# MCU_Schematic.net
KiCad netlist of a schematic drawn in Altium Designer
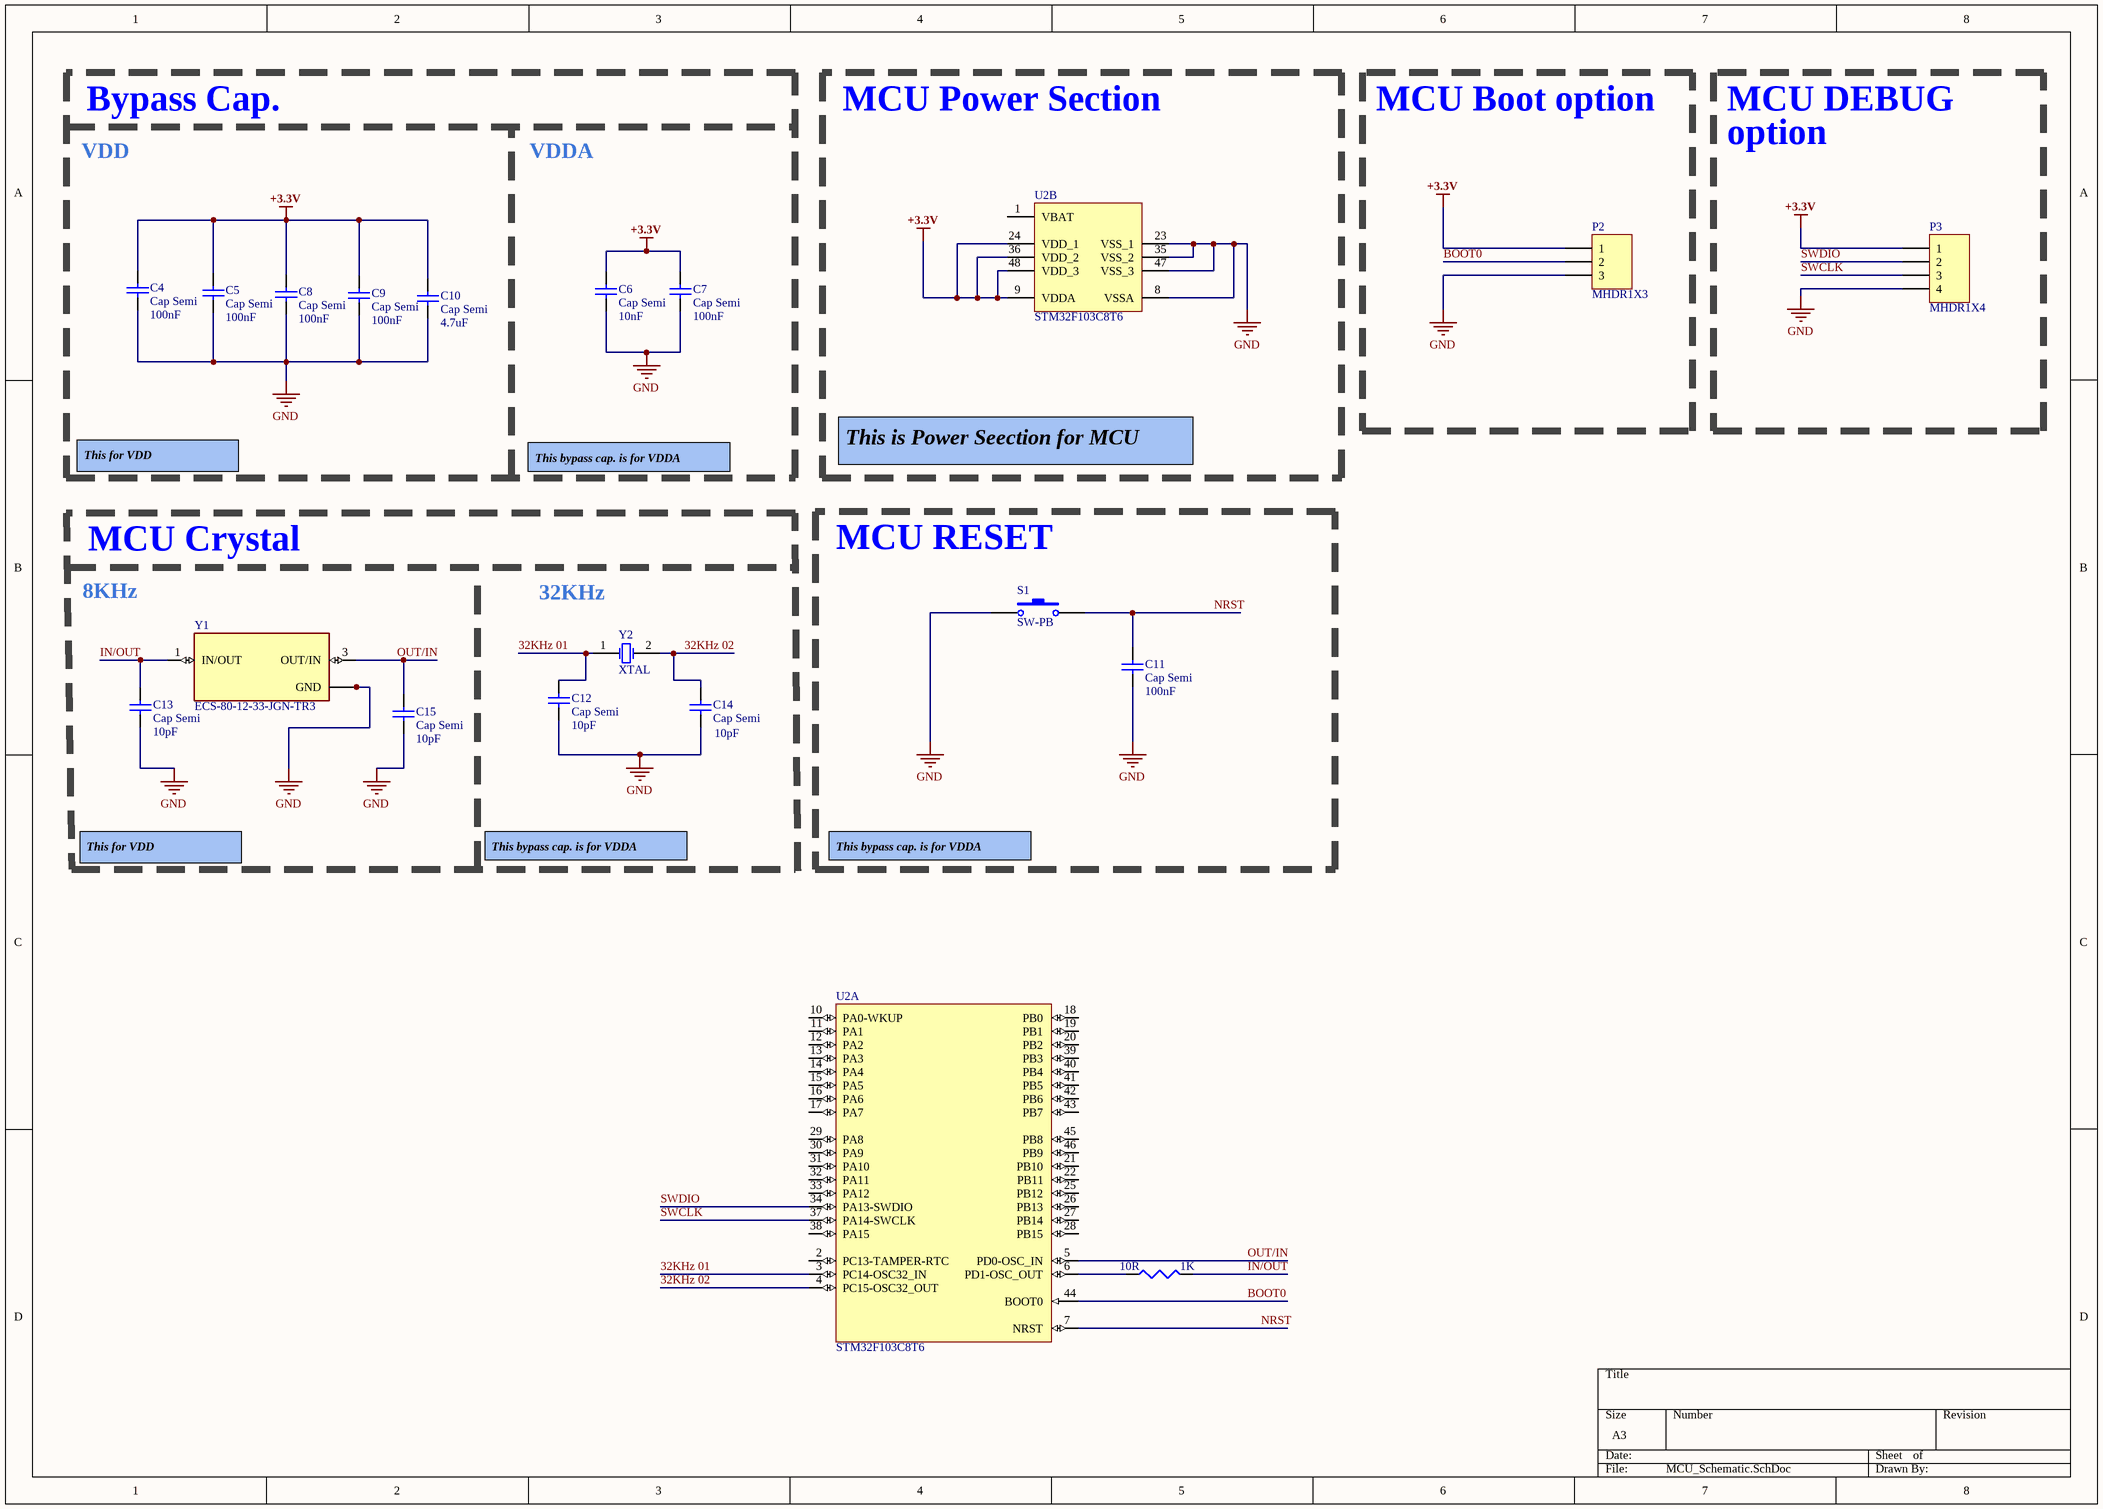
[diagram p0: MCU_Schematic.SchDoc]

(export (version "E")
  (design (tool "Eeschema 10.0.6"))
  (components
    (comp (ref "10R")
      (value "1K")
      (footprint "J1-0603")
      (description "Resistor")
      (fields (field (name "Comment") "Res3") (field (name "PUBLISHER") "Altium Limited"))
      (libsource (lib "Miscellaneous Devices") (part "Res3"))
    )
    (comp (ref "C4")
      (value "Cap Semi")
      (footprint "1608[0603]")
      (description "Capacitor (Semiconductor SIM Model)")
      (fields (field (name "ALTIUM_VALUE") "100nF") (field (name "PUBLISHER") "Altium Limited"))
      (libsource (lib "Miscellaneous Devices") (part "Cap Semi"))
    )
    (comp (ref "C5")
      (value "Cap Semi")
      (footprint "1608[0603]")
      (description "Capacitor (Semiconductor SIM Model)")
      (fields (field (name "ALTIUM_VALUE") "100nF") (field (name "PUBLISHER") "Altium Limited"))
      (libsource (lib "Miscellaneous Devices") (part "Cap Semi"))
    )
    (comp (ref "C6")
      (value "Cap Semi")
      (footprint "1608[0603]")
      (description "Capacitor (Semiconductor SIM Model)")
      (fields (field (name "ALTIUM_VALUE") "10nF") (field (name "PUBLISHER") "Altium Limited"))
      (libsource (lib "Miscellaneous Devices") (part "Cap Semi"))
    )
    (comp (ref "C7")
      (value "Cap Semi")
      (footprint "1608[0603]")
      (description "Capacitor (Semiconductor SIM Model)")
      (fields (field (name "ALTIUM_VALUE") "100nF") (field (name "PUBLISHER") "Altium Limited"))
      (libsource (lib "Miscellaneous Devices") (part "Cap Semi"))
    )
    (comp (ref "C8")
      (value "Cap Semi")
      (footprint "1608[0603]")
      (description "Capacitor (Semiconductor SIM Model)")
      (fields (field (name "ALTIUM_VALUE") "100nF") (field (name "PUBLISHER") "Altium Limited"))
      (libsource (lib "Miscellaneous Devices") (part "Cap Semi"))
    )
    (comp (ref "C9")
      (value "Cap Semi")
      (footprint "1608[0603]")
      (description "Capacitor (Semiconductor SIM Model)")
      (fields (field (name "ALTIUM_VALUE") "100nF") (field (name "PUBLISHER") "Altium Limited"))
      (libsource (lib "Miscellaneous Devices") (part "Cap Semi"))
    )
    (comp (ref "C10")
      (value "Cap Semi")
      (footprint "1608[0603]")
      (description "Capacitor (Semiconductor SIM Model)")
      (fields (field (name "ALTIUM_VALUE") "4.7uF") (field (name "PUBLISHER") "Altium Limited"))
      (libsource (lib "Miscellaneous Devices") (part "Cap Semi"))
    )
    (comp (ref "C11")
      (value "Cap Semi")
      (footprint "1608[0603]")
      (description "Capacitor (Semiconductor SIM Model)")
      (fields (field (name "ALTIUM_VALUE") "100nF") (field (name "PUBLISHER") "Altium Limited"))
      (libsource (lib "Miscellaneous Devices") (part "Cap Semi"))
    )
    (comp (ref "C12")
      (value "Cap Semi")
      (footprint "0402")
      (description "Capacitor (Semiconductor SIM Model)")
      (fields (field (name "ALTIUM_VALUE") "10pF") (field (name "PUBLISHER") "Altium Limited"))
      (libsource (lib "Miscellaneous Devices") (part "Cap Semi"))
    )
    (comp (ref "C13")
      (value "Cap Semi")
      (footprint "0402")
      (description "Capacitor (Semiconductor SIM Model)")
      (fields (field (name "ALTIUM_VALUE") "10pF") (field (name "PUBLISHER") "Altium Limited"))
      (libsource (lib "Miscellaneous Devices") (part "Cap Semi"))
    )
    (comp (ref "C14")
      (value "Cap Semi")
      (footprint "0402")
      (description "Capacitor (Semiconductor SIM Model)")
      (fields (field (name "ALTIUM_VALUE") "10pF") (field (name "PUBLISHER") "Altium Limited"))
      (libsource (lib "Miscellaneous Devices") (part "Cap Semi"))
    )
    (comp (ref "C15")
      (value "Cap Semi")
      (footprint "0402")
      (description "Capacitor (Semiconductor SIM Model)")
      (fields (field (name "ALTIUM_VALUE") "10pF") (field (name "PUBLISHER") "Altium Limited"))
      (libsource (lib "Miscellaneous Devices") (part "Cap Semi"))
    )
    (comp (ref "P2")
      (value "MHDR1X3")
      (footprint "MHDR1X3")
      (description "Header, 3-Pin")
      (fields (field (name "PUBLISHER") "Altium Limited"))
      (libsource (lib "Miscellaneous Connectors") (part "MHDR1X3"))
    )
    (comp (ref "P3")
      (value "MHDR1X4")
      (footprint "MHDR1X4")
      (description "Header, 4-Pin")
      (fields (field (name "PUBLISHER") "Altium Limited"))
      (libsource (lib "Miscellaneous Connectors") (part "MHDR1X4"))
    )
    (comp (ref "S1")
      (value "SW-PB")
      (footprint "SPST-2")
      (description "Switch")
      (fields (field (name "PUBLISHER") "Altium Limited"))
      (libsource (lib "Miscellaneous Devices") (part "SW-PB"))
    )
    (comp (ref "U2")
      (value "STM32F103C8T6")
      (footprint "LQFP48_N")
      (libsource (lib "STMicroelectronics STM32 F1") (part "STM32F103C8T6"))
    )
    (comp (ref "Y1")
      (value "ECS-80-12-33-JGN-TR3")
      (footprint "XTAL_ECS-240-8-33-AGN-TR")
      (description "Crystal 8MHz Â±20ppm (Tol) Â±30ppm (Stability) 12pF FUND 400Ohm 4-Pin Mini-CSMD T/R")
      (fields (field (name "MF") "ECS Inc."))
      (libsource (lib "ECS-80-12-33-JGN-TR3") (part "ECS-80-12-33-JGN-TR3"))
    )
    (comp (ref "Y2")
      (value "XTAL")
      (footprint "R38")
      (description "Crystal Oscillator")
      (fields (field (name "PUBLISHER") "Altium Limited"))
      (libsource (lib "Miscellaneous Devices") (part "XTAL"))
    )
  )
  (nets
    (net (code "1") (name "+3.3V") (class "Default")
      (node (ref "C10") (pin "2") (pinfunction "2_2") (pintype "passive"))
      (node (ref "C4") (pin "1") (pinfunction "1_1") (pintype "passive"))
      (node (ref "C5") (pin "2") (pinfunction "2_2") (pintype "passive"))
      (node (ref "C6") (pin "2") (pinfunction "2_2") (pintype "passive"))
      (node (ref "C7") (pin "2") (pinfunction "2_2") (pintype "passive"))
      (node (ref "C8") (pin "2") (pinfunction "2_2") (pintype "passive"))
      (node (ref "C9") (pin "2") (pinfunction "2_2") (pintype "passive"))
      (node (ref "P2") (pin "1") (pinfunction "1_1") (pintype "passive"))
      (node (ref "P3") (pin "1") (pinfunction "1_1") (pintype "passive"))
      (node (ref "U2") (pin "24") (pinfunction "VDD_1_24") (pintype "power_in"))
      (node (ref "U2") (pin "36") (pinfunction "VDD_2_36") (pintype "power_in"))
      (node (ref "U2") (pin "48") (pinfunction "VDD_3_48") (pintype "power_in"))
      (node (ref "U2") (pin "9") (pinfunction "VDDA_9") (pintype "power_in"))
    )
    (net (code "2") (name "/32KHz 01") (class "Default")
      (node (ref "C12") (pin "2") (pinfunction "2_2") (pintype "passive"))
      (node (ref "U2") (pin "3") (pinfunction "PC14-OSC32_IN_3") (pintype "bidirectional"))
      (node (ref "Y2") (pin "1") (pinfunction "OSC1_1") (pintype "passive"))
    )
    (net (code "3") (name "/32KHz 02") (class "Default")
      (node (ref "C14") (pin "2") (pinfunction "2_2") (pintype "passive"))
      (node (ref "U2") (pin "4") (pinfunction "PC15-OSC32_OUT_4") (pintype "bidirectional"))
      (node (ref "Y2") (pin "2") (pinfunction "OSC2_2") (pintype "passive"))
    )
    (net (code "4") (name "/BOOT0") (class "Default")
      (node (ref "P2") (pin "2") (pinfunction "2_2") (pintype "passive"))
      (node (ref "U2") (pin "44") (pinfunction "BOOT0_44") (pintype "input"))
    )
    (net (code "5") (name "/IN{slash}OUT") (class "Default")
      (node (ref "10R") (pin "2") (pinfunction "2_2") (pintype "passive"))
      (node (ref "C13") (pin "2") (pinfunction "2_2") (pintype "passive"))
      (node (ref "Y1") (pin "1") (pinfunction "IN/OUT_1") (pintype "bidirectional"))
    )
    (net (code "6") (name "/NRST") (class "Default")
      (node (ref "C11") (pin "2") (pinfunction "2_2") (pintype "passive"))
      (node (ref "S1") (pin "2") (pinfunction "2_2") (pintype "passive"))
      (node (ref "U2") (pin "7") (pinfunction "NRST_7") (pintype "bidirectional"))
    )
    (net (code "7") (name "/OUT{slash}IN") (class "Default")
      (node (ref "C15") (pin "2") (pinfunction "2_2") (pintype "passive"))
      (node (ref "U2") (pin "5") (pinfunction "PD0-OSC_IN_5") (pintype "bidirectional"))
      (node (ref "Y1") (pin "3") (pinfunction "OUT/IN_3") (pintype "bidirectional"))
    )
    (net (code "8") (name "/SWCLK") (class "Default")
      (node (ref "P3") (pin "3") (pinfunction "3_3") (pintype "passive"))
      (node (ref "U2") (pin "37") (pinfunction "PA14_37") (pintype "bidirectional"))
    )
    (net (code "9") (name "/SWDIO") (class "Default")
      (node (ref "P3") (pin "2") (pinfunction "2_2") (pintype "passive"))
      (node (ref "U2") (pin "34") (pinfunction "PA13_34") (pintype "bidirectional"))
    )
    (net (code "10") (name "GND") (class "Default")
      (node (ref "C10") (pin "1") (pinfunction "1_1") (pintype "passive"))
      (node (ref "C11") (pin "1") (pinfunction "1_1") (pintype "passive"))
      (node (ref "C12") (pin "1") (pinfunction "1_1") (pintype "passive"))
      (node (ref "C13") (pin "1") (pinfunction "1_1") (pintype "passive"))
      (node (ref "C14") (pin "1") (pinfunction "1_1") (pintype "passive"))
      (node (ref "C15") (pin "1") (pinfunction "1_1") (pintype "passive"))
      (node (ref "C4") (pin "2") (pinfunction "2_2") (pintype "passive"))
      (node (ref "C5") (pin "1") (pinfunction "1_1") (pintype "passive"))
      (node (ref "C6") (pin "1") (pinfunction "1_1") (pintype "passive"))
      (node (ref "C7") (pin "1") (pinfunction "1_1") (pintype "passive"))
      (node (ref "C8") (pin "1") (pinfunction "1_1") (pintype "passive"))
      (node (ref "C9") (pin "1") (pinfunction "1_1") (pintype "passive"))
      (node (ref "P2") (pin "3") (pinfunction "3_3") (pintype "passive"))
      (node (ref "P3") (pin "4") (pinfunction "4_4") (pintype "passive"))
      (node (ref "S1") (pin "1") (pinfunction "1_1") (pintype "passive"))
      (node (ref "U2") (pin "23") (pinfunction "VSS_1_23") (pintype "power_in"))
      (node (ref "U2") (pin "35") (pinfunction "VSS_2_35") (pintype "power_in"))
      (node (ref "U2") (pin "47") (pinfunction "VSS_3_47") (pintype "power_in"))
      (node (ref "U2") (pin "8") (pinfunction "VSSA_8") (pintype "power_in"))
      (node (ref "Y1") (pin "2") (pinfunction "GND_2") (pintype "power_in"))
      (node (ref "Y1") (pin "4") (pinfunction "GND_4") (pintype "power_in"))
    )
    (net (code "11") (name "Net-(U2A-PD1)") (class "Default")
      (node (ref "10R") (pin "1") (pinfunction "1_1") (pintype "passive"))
      (node (ref "U2") (pin "6") (pinfunction "PD1_6") (pintype "bidirectional"))
    )
    (net (code "12") (name "unconnected-(U2A-PA0-WKUP-Pad10)") (class "Default")
      (node (ref "U2") (pin "10") (pinfunction "PA0-WKUP_10") (pintype "bidirectional"))
    )
    (net (code "13") (name "unconnected-(U2A-PA1-Pad11)") (class "Default")
      (node (ref "U2") (pin "11") (pinfunction "PA1_11") (pintype "bidirectional"))
    )
    (net (code "14") (name "unconnected-(U2A-PA2-Pad12)") (class "Default")
      (node (ref "U2") (pin "12") (pinfunction "PA2_12") (pintype "bidirectional"))
    )
    (net (code "15") (name "unconnected-(U2A-PA3-Pad13)") (class "Default")
      (node (ref "U2") (pin "13") (pinfunction "PA3_13") (pintype "bidirectional"))
    )
    (net (code "16") (name "unconnected-(U2A-PA4-Pad14)") (class "Default")
      (node (ref "U2") (pin "14") (pinfunction "PA4_14") (pintype "bidirectional"))
    )
    (net (code "17") (name "unconnected-(U2A-PA5-Pad15)") (class "Default")
      (node (ref "U2") (pin "15") (pinfunction "PA5_15") (pintype "bidirectional"))
    )
    (net (code "18") (name "unconnected-(U2A-PA6-Pad16)") (class "Default")
      (node (ref "U2") (pin "16") (pinfunction "PA6_16") (pintype "bidirectional"))
    )
    (net (code "19") (name "unconnected-(U2A-PA7-Pad17)") (class "Default")
      (node (ref "U2") (pin "17") (pinfunction "PA7_17") (pintype "bidirectional"))
    )
    (net (code "20") (name "unconnected-(U2A-PA8-Pad29)") (class "Default")
      (node (ref "U2") (pin "29") (pinfunction "PA8_29") (pintype "bidirectional"))
    )
    (net (code "21") (name "unconnected-(U2A-PA9-Pad30)") (class "Default")
      (node (ref "U2") (pin "30") (pinfunction "PA9_30") (pintype "bidirectional"))
    )
    (net (code "22") (name "unconnected-(U2A-PA10-Pad31)") (class "Default")
      (node (ref "U2") (pin "31") (pinfunction "PA10_31") (pintype "bidirectional"))
    )
    (net (code "23") (name "unconnected-(U2A-PA11-Pad32)") (class "Default")
      (node (ref "U2") (pin "32") (pinfunction "PA11_32") (pintype "bidirectional"))
    )
    (net (code "24") (name "unconnected-(U2A-PA12-Pad33)") (class "Default")
      (node (ref "U2") (pin "33") (pinfunction "PA12_33") (pintype "bidirectional"))
    )
    (net (code "25") (name "unconnected-(U2A-PA15-Pad38)") (class "Default")
      (node (ref "U2") (pin "38") (pinfunction "PA15_38") (pintype "bidirectional"))
    )
    (net (code "26") (name "unconnected-(U2A-PB0-Pad18)") (class "Default")
      (node (ref "U2") (pin "18") (pinfunction "PB0_18") (pintype "bidirectional"))
    )
    (net (code "27") (name "unconnected-(U2A-PB1-Pad19)") (class "Default")
      (node (ref "U2") (pin "19") (pinfunction "PB1_19") (pintype "bidirectional"))
    )
    (net (code "28") (name "unconnected-(U2A-PB2-Pad20)") (class "Default")
      (node (ref "U2") (pin "20") (pinfunction "PB2_20") (pintype "bidirectional"))
    )
    (net (code "29") (name "unconnected-(U2A-PB3-Pad39)") (class "Default")
      (node (ref "U2") (pin "39") (pinfunction "PB3_39") (pintype "bidirectional"))
    )
    (net (code "30") (name "unconnected-(U2A-PB4-Pad40)") (class "Default")
      (node (ref "U2") (pin "40") (pinfunction "PB4_40") (pintype "bidirectional"))
    )
    (net (code "31") (name "unconnected-(U2A-PB5-Pad41)") (class "Default")
      (node (ref "U2") (pin "41") (pinfunction "PB5_41") (pintype "bidirectional"))
    )
    (net (code "32") (name "unconnected-(U2A-PB6-Pad42)") (class "Default")
      (node (ref "U2") (pin "42") (pinfunction "PB6_42") (pintype "bidirectional"))
    )
    (net (code "33") (name "unconnected-(U2A-PB7-Pad43)") (class "Default")
      (node (ref "U2") (pin "43") (pinfunction "PB7_43") (pintype "bidirectional"))
    )
    (net (code "34") (name "unconnected-(U2A-PB8-Pad45)") (class "Default")
      (node (ref "U2") (pin "45") (pinfunction "PB8_45") (pintype "bidirectional"))
    )
    (net (code "35") (name "unconnected-(U2A-PB9-Pad46)") (class "Default")
      (node (ref "U2") (pin "46") (pinfunction "PB9_46") (pintype "bidirectional"))
    )
    (net (code "36") (name "unconnected-(U2A-PB10-Pad21)") (class "Default")
      (node (ref "U2") (pin "21") (pinfunction "PB10_21") (pintype "bidirectional"))
    )
    (net (code "37") (name "unconnected-(U2A-PB11-Pad22)") (class "Default")
      (node (ref "U2") (pin "22") (pinfunction "PB11_22") (pintype "bidirectional"))
    )
    (net (code "38") (name "unconnected-(U2A-PB12-Pad25)") (class "Default")
      (node (ref "U2") (pin "25") (pinfunction "PB12_25") (pintype "bidirectional"))
    )
    (net (code "39") (name "unconnected-(U2A-PB13-Pad26)") (class "Default")
      (node (ref "U2") (pin "26") (pinfunction "PB13_26") (pintype "bidirectional"))
    )
    (net (code "40") (name "unconnected-(U2A-PB14-Pad27)") (class "Default")
      (node (ref "U2") (pin "27") (pinfunction "PB14_27") (pintype "bidirectional"))
    )
    (net (code "41") (name "unconnected-(U2A-PB15-Pad28)") (class "Default")
      (node (ref "U2") (pin "28") (pinfunction "PB15_28") (pintype "bidirectional"))
    )
    (net (code "42") (name "unconnected-(U2A-PC13-TAMPER-RTC-Pad2)") (class "Default")
      (node (ref "U2") (pin "2") (pinfunction "PC13-TAMPER-RTC_2") (pintype "bidirectional"))
    )
    (net (code "43") (name "unconnected-(U2B-VBAT-Pad1)") (class "Default")
      (node (ref "U2") (pin "1") (pinfunction "VBAT_1") (pintype "power_in"))
    )
  )
)
